# nRF52832.net
KiCad netlist of a schematic drawn in Altium Designer
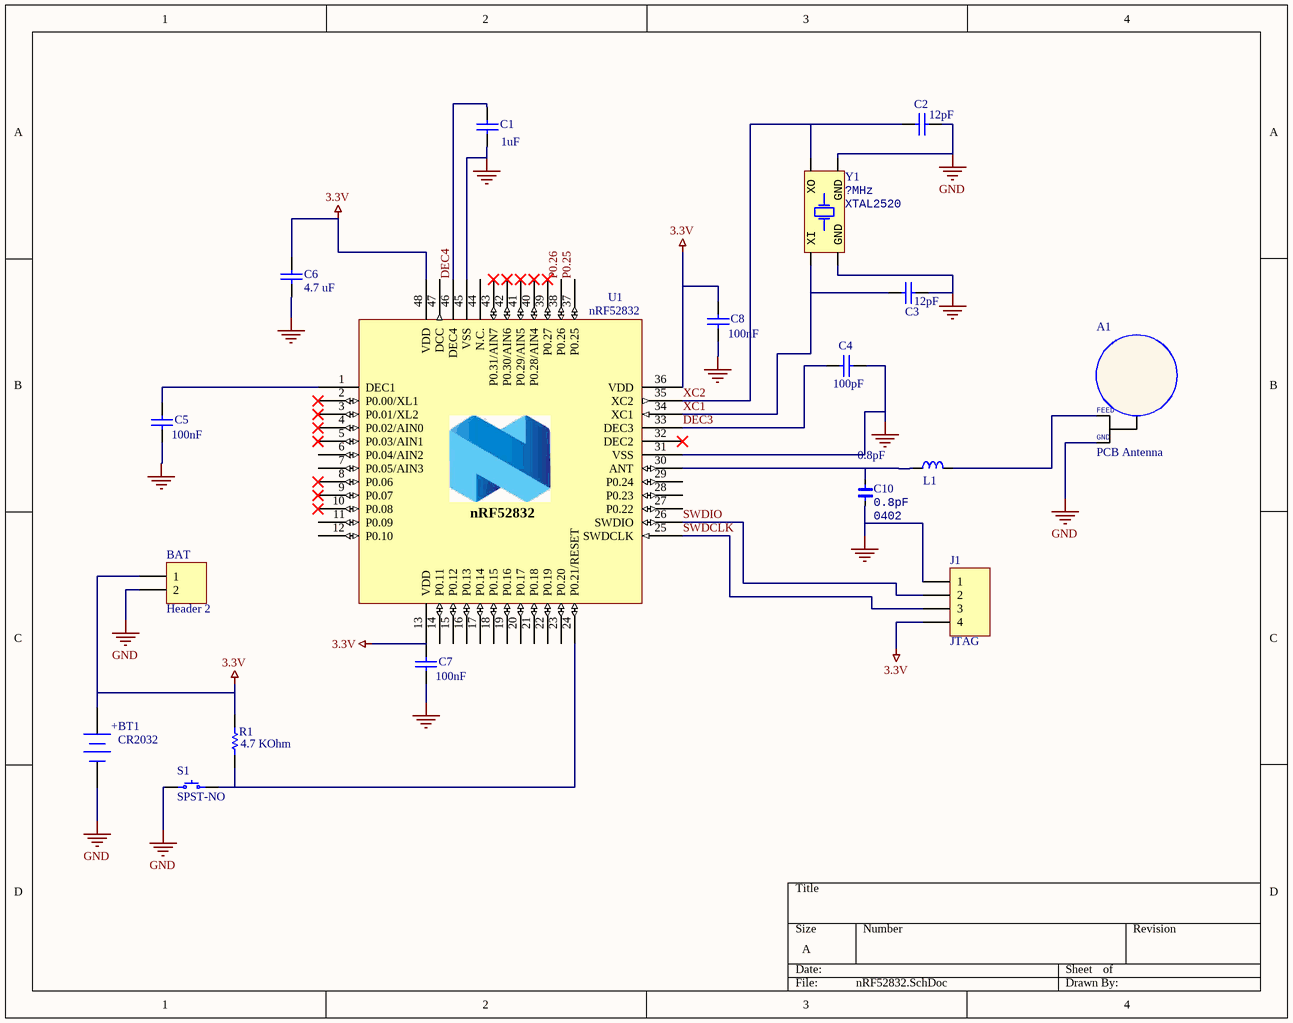
[diagram p0: nRF52832.SchDoc]

(export (version "E")
  (design (tool "Eeschema 10.0.6"))
  (components
    (comp (ref "A1")
      (value "PCB Antenna")
      (footprint "BLE_MIFA")
      (libsource (lib "Antenna") (part "BLE_MIFA"))
    )
    (comp (ref "BAT")
      (value "Header 2")
      (footprint "HDR1X2")
      (description "Header, 2-Pin")
      (libsource (lib "Miscellaneous Connectors") (part "Header 2"))
    )
    (comp (ref "BT1")
      (value "CR2032")
      (footprint "CR2032-1")
      (description "CR2032 Cell Holder")
      (fields (field (name "PUBLISHER") "Cynetik Group"))
      (libsource (lib "Battery Holder") (part "CR2032 Cell Holder"))
    )
    (comp (ref "C1")
      (value "1uF")
      (footprint "CAPC1608X90X35LL10T15")
      (fields
        (field (name "MANUFACTURER") "Murata")
        (field (name "PART NUMBER") "GRM188R61E105KA12D")
        (field (name "TOLERANCE") "10%")
      )
      (libsource (lib "Altium Content Vault") (part "CAP"))
    )
    (comp (ref "C2")
      (value "12pF")
      (footprint "CAPC1005X55X25ML05T10")
      (fields
        (field (name "PART NUMBER") "GRM1555C1H120GA01D")
        (field (name "MANUFACTURER") "Murata")
        (field (name "TOLERANCE") "2%")
      )
      (libsource (lib "Altium Content Vault") (part "CAP"))
    )
    (comp (ref "C3")
      (value "12pF")
      (footprint "CAPC1005X55X25ML05T10")
      (fields
        (field (name "PART NUMBER") "GRM1555C1H120GA01D")
        (field (name "MANUFACTURER") "Murata")
        (field (name "TOLERANCE") "2%")
      )
      (libsource (lib "Altium Content Vault") (part "CAP"))
    )
    (comp (ref "C4")
      (value "100pF")
      (footprint "CAPC1005X55X25ML05T10")
      (fields
        (field (name "MANUFACTURER") "Murata")
        (field (name "PART NUMBER") "GRM1555C1H101JA01D")
        (field (name "TOLERANCE") "5%")
      )
      (libsource (lib "Altium Content Vault") (part "CAP"))
    )
    (comp (ref "C5")
      (value "100nF")
      (footprint "CAPC1005X55X30LL05T10")
      (fields
        (field (name "MANUFACTURER") "Kemet")
        (field (name "PART NUMBER") "C0402C104K4RACTU")
        (field (name "MANUFACTURER PART NUMBER") "C0402C104K4RAC-TU")
      )
      (libsource (lib "Altium Content Vault") (part "CAP"))
    )
    (comp (ref "C6")
      (value "4.7 uF")
      (footprint "CAPC1608X90X35NL10T15")
      (description "Chip Capacitor, 4.7 uF, +/- 10%, 6.3 V, -55 to 85 degC, 0603 (1608 Metric), RoHS, Tape and Reel")
      (fields (field (name "PARTNUMBER") "GRM188R60J475KE19D") (field (name "TOLERANCE") "10%"))
      (libsource (lib "Altium Content Vault") (part "CAP-NP-2"))
    )
    (comp (ref "C7")
      (value "100nF")
      (footprint "CAPC1005X55X30LL05T10")
      (fields
        (field (name "MANUFACTURER") "Kemet")
        (field (name "PART NUMBER") "C0402C104K4RACTU")
        (field (name "MANUFACTURER PART NUMBER") "C0402C104K4RAC-TU")
      )
      (libsource (lib "Altium Content Vault") (part "CAP"))
    )
    (comp (ref "C8")
      (value "100nF")
      (footprint "CAPC1005X55X30LL05T10")
      (fields
        (field (name "MANUFACTURER") "Kemet")
        (field (name "PART NUMBER") "C0402C104K4RACTU")
        (field (name "MANUFACTURER PART NUMBER") "C0402C104K4RAC-TU")
      )
      (libsource (lib "Altium Content Vault") (part "CAP"))
    )
    (comp (ref "C10")
      (value "0.8pF")
      (footprint "0402_1x0.5x0.5mm")
      (description "Capacitor")
      (fields
        (field (name "TYPE") "0402")
        (field (name "MANUFACTURER PART NUMBER") "04023J0R8ABSTR")
        (field (name "CAPACITANCE") "0.8pF")
        (field (name "VOLTAGE") "25V")
      )
      (libsource (lib "Capacitors") (part "Cap_0402"))
    )
    (comp (ref "J1") (value "JTAG") (footprint "HDR1X4") (libsource (lib "Connectors") (part "JTAG")))
    (comp (ref "L1")
      (value "SMD_Inductor")
      (footprint "FER 0402/1005")
      (libsource (lib "Inductor") (part "SMD_Inductor"))
    )
    (comp (ref "R1")
      (value "4.7 KOhm")
      (footprint "RESC1005X40X25LL05T05")
      (description "Chip Resistor, 4.7 KOhm, +/- 1%, 63 mW, -55 to 155 degC, 0402 (1005 Metric), RoHS, Tape and Reel")
      (fields (field (name "PARTNUMBER") "CRCW04024K70FKED") (field (name "TOLERANCE") "1%"))
      (libsource (lib "Altium Content Vault") (part "RES"))
    )
    (comp (ref "S1")
      (value "SPST-NO")
      (footprint "C&K KXT")
      (fields (field (name "MANUFACTURER PART NUMBER") "KXT 331 LHS"))
      (libsource (lib "Button") (part "SPST-NO 2 PIN"))
    )
    (comp (ref "U1")
      (value "nRF52832")
      (footprint "nRF52832_QFAA")
      (fields
        (field (name "MANUFACTURER") "Nordic Semiconductor")
        (field (name "MANUFACTURER PART NUMBER") "NRF52832-QFAA-R7")
      )
      (libsource (lib "IC") (part "nRF52832_QFN"))
    )
    (comp (ref "Y1")
      (value "?MHz")
      (footprint "XT_2520_4")
      (description "Crystal Oscillator")
      (fields (field (name "TYPE") "XTAL2520") (field (name "Comment") "XTAL2520"))
      (libsource (lib "Quartz crystals") (part "XTAL_2520_4P"))
    )
  )
  (nets
    (net (code "1") (name "/DEC3") (class "Default")
      (node (ref "C4") (pin "1") (pinfunction "1_1") (pintype "passive"))
      (node (ref "U1") (pin "33") (pinfunction "DEC3_33") (pintype "power_in"))
    )
    (net (code "2") (name "/DEC4") (class "Default")
      (node (ref "C1") (pin "2") (pinfunction "2_2") (pintype "passive"))
      (node (ref "U1") (pin "46") (pinfunction "DEC4_46") (pintype "power_in"))
    )
    (net (code "3") (name "/P0.25") (class "Default")
      (node (ref "U1") (pin "37") (pinfunction "P0.25_37") (pintype "bidirectional"))
    )
    (net (code "4") (name "/P0.26") (class "Default")
      (node (ref "U1") (pin "38") (pinfunction "P0.26_38") (pintype "bidirectional"))
    )
    (net (code "5") (name "/SWDCLK") (class "Default")
      (node (ref "J1") (pin "3") (pinfunction "3_3") (pintype "passive"))
      (node (ref "U1") (pin "25") (pinfunction "SWDCLK_25") (pintype "input"))
    )
    (net (code "6") (name "/SWDIO") (class "Default")
      (node (ref "J1") (pin "2") (pinfunction "2_2") (pintype "passive"))
      (node (ref "U1") (pin "26") (pinfunction "SWDIO_26") (pintype "bidirectional"))
    )
    (net (code "7") (name "/XC1") (class "Default")
      (node (ref "C3") (pin "1") (pinfunction "1_1") (pintype "passive"))
      (node (ref "U1") (pin "34") (pinfunction "XC1_34") (pintype "input"))
      (node (ref "Y1") (pin "1") (pinfunction "XI_1") (pintype "passive"))
    )
    (net (code "8") (name "/XC2") (class "Default")
      (node (ref "C2") (pin "1") (pinfunction "1_1") (pintype "passive"))
      (node (ref "U1") (pin "35") (pinfunction "XC2_35") (pintype "output"))
      (node (ref "Y1") (pin "3") (pinfunction "XO_3") (pintype "passive"))
    )
    (net (code "9") (name "3.3V") (class "Default")
      (node (ref "BAT") (pin "1") (pinfunction "1_1") (pintype "passive"))
      (node (ref "BT1") (pin "1") (pinfunction "+_1") (pintype "passive"))
      (node (ref "C6") (pin "2") (pinfunction "2_2") (pintype "passive"))
      (node (ref "C7") (pin "2") (pinfunction "2_2") (pintype "passive"))
      (node (ref "C8") (pin "2") (pinfunction "2_2") (pintype "passive"))
      (node (ref "J1") (pin "4") (pinfunction "4_4") (pintype "passive"))
      (node (ref "R1") (pin "2") (pinfunction "2_2") (pintype "passive"))
      (node (ref "U1") (pin "13") (pinfunction "VDD_13") (pintype "power_in"))
      (node (ref "U1") (pin "36") (pinfunction "VDD_36") (pintype "power_in"))
      (node (ref "U1") (pin "48") (pinfunction "VDD_48") (pintype "power_in"))
    )
    (net (code "10") (name "GND") (class "Default")
      (node (ref "A1") (pin "0") (pinfunction "GND_0") (pintype "passive"))
      (node (ref "BAT") (pin "2") (pinfunction "2_2") (pintype "passive"))
      (node (ref "BT1") (pin "2") (pinfunction "-_2") (pintype "passive"))
      (node (ref "C1") (pin "1") (pinfunction "1_1") (pintype "passive"))
      (node (ref "C10") (pin "1") (pinfunction "1_1") (pintype "passive"))
      (node (ref "C2") (pin "2") (pinfunction "2_2") (pintype "passive"))
      (node (ref "C3") (pin "2") (pinfunction "2_2") (pintype "passive"))
      (node (ref "C4") (pin "2") (pinfunction "2_2") (pintype "passive"))
      (node (ref "C5") (pin "1") (pinfunction "1_1") (pintype "passive"))
      (node (ref "C6") (pin "1") (pinfunction "1_1") (pintype "passive"))
      (node (ref "C7") (pin "1") (pinfunction "1_1") (pintype "passive"))
      (node (ref "C8") (pin "1") (pinfunction "1_1") (pintype "passive"))
      (node (ref "J1") (pin "1") (pinfunction "1_1") (pintype "passive"))
      (node (ref "S1") (pin "1") (pinfunction "1_1") (pintype "passive"))
      (node (ref "U1") (pin "31") (pinfunction "VSS_31") (pintype "power_in"))
      (node (ref "U1") (pin "45") (pinfunction "VSS_45") (pintype "power_in"))
      (node (ref "Y1") (pin "2") (pinfunction "GND_2") (pintype "passive"))
      (node (ref "Y1") (pin "4") (pinfunction "GND_4") (pintype "passive"))
    )
    (net (code "11") (name "Net-(A1-Feed)") (class "Default")
      (node (ref "A1") (pin "1") (pinfunction "Feed_1") (pintype "passive"))
      (node (ref "L1") (pin "2") (pinfunction "2_2") (pintype "passive"))
    )
    (net (code "12") (name "Net-(U1-ANT)") (class "Default")
      (node (ref "C10") (pin "2") (pinfunction "2_2") (pintype "passive"))
      (node (ref "L1") (pin "1") (pinfunction "1_1") (pintype "passive"))
      (node (ref "U1") (pin "30") (pinfunction "ANT_30") (pintype "bidirectional"))
    )
    (net (code "13") (name "Net-(U1-DEC1)") (class "Default")
      (node (ref "C5") (pin "2") (pinfunction "2_2") (pintype "passive"))
      (node (ref "U1") (pin "1") (pinfunction "DEC1_1") (pintype "power_in"))
    )
    (net (code "14") (name "Net-(U1-P0.21{slash}RESET)") (class "Default")
      (node (ref "R1") (pin "1") (pinfunction "1_1") (pintype "passive"))
      (node (ref "S1") (pin "2") (pinfunction "2_2") (pintype "passive"))
      (node (ref "U1") (pin "24") (pinfunction "P0.21/RESET_24") (pintype "bidirectional"))
    )
    (net (code "15") (name "unconnected-(U1-DCC-Pad47)") (class "Default")
      (node (ref "U1") (pin "47") (pinfunction "DCC_47") (pintype "output"))
    )
    (net (code "16") (name "unconnected-(U1-DEC2-Pad32)") (class "Default")
      (node (ref "U1") (pin "32") (pinfunction "DEC2_32") (pintype "power_in+no_connect"))
    )
    (net (code "17") (name "unconnected-(U1-N.C.-Pad44)") (class "Default")
      (node (ref "U1") (pin "44") (pinfunction "N.C._44") (pintype "power_in"))
    )
    (net (code "18") (name "unconnected-(U1-P0.00{slash}XL1-Pad2)") (class "Default")
      (node (ref "U1") (pin "2") (pinfunction "P0.00/XL1_2") (pintype "bidirectional+no_connect"))
    )
    (net (code "19") (name "unconnected-(U1-P0.01{slash}XL2-Pad3)") (class "Default")
      (node (ref "U1") (pin "3") (pinfunction "P0.01/XL2_3") (pintype "bidirectional+no_connect"))
    )
    (net (code "20") (name "unconnected-(U1-P0.02{slash}AIN0-Pad4)") (class "Default")
      (node (ref "U1") (pin "4") (pinfunction "P0.02/AIN0_4") (pintype "bidirectional+no_connect"))
    )
    (net (code "21") (name "unconnected-(U1-P0.03{slash}AIN1-Pad5)") (class "Default")
      (node (ref "U1") (pin "5") (pinfunction "P0.03/AIN1_5") (pintype "bidirectional+no_connect"))
    )
    (net (code "22") (name "unconnected-(U1-P0.04{slash}AIN2-Pad6)") (class "Default")
      (node (ref "U1") (pin "6") (pinfunction "P0.04/AIN2_6") (pintype "bidirectional"))
    )
    (net (code "23") (name "unconnected-(U1-P0.05{slash}AIN3-Pad7)") (class "Default")
      (node (ref "U1") (pin "7") (pinfunction "P0.05/AIN3_7") (pintype "bidirectional"))
    )
    (net (code "24") (name "unconnected-(U1-P0.06-Pad8)") (class "Default")
      (node (ref "U1") (pin "8") (pinfunction "P0.06_8") (pintype "bidirectional+no_connect"))
    )
    (net (code "25") (name "unconnected-(U1-P0.07-Pad9)") (class "Default")
      (node (ref "U1") (pin "9") (pinfunction "P0.07_9") (pintype "bidirectional+no_connect"))
    )
    (net (code "26") (name "unconnected-(U1-P0.08-Pad10)") (class "Default")
      (node (ref "U1") (pin "10") (pinfunction "P0.08_10") (pintype "bidirectional+no_connect"))
    )
    (net (code "27") (name "unconnected-(U1-P0.09-Pad11)") (class "Default")
      (node (ref "U1") (pin "11") (pinfunction "P0.09_11") (pintype "bidirectional"))
    )
    (net (code "28") (name "unconnected-(U1-P0.10-Pad12)") (class "Default")
      (node (ref "U1") (pin "12") (pinfunction "P0.10_12") (pintype "bidirectional"))
    )
    (net (code "29") (name "unconnected-(U1-P0.11-Pad14)") (class "Default")
      (node (ref "U1") (pin "14") (pinfunction "P0.11_14") (pintype "bidirectional"))
    )
    (net (code "30") (name "unconnected-(U1-P0.12-Pad15)") (class "Default")
      (node (ref "U1") (pin "15") (pinfunction "P0.12_15") (pintype "bidirectional"))
    )
    (net (code "31") (name "unconnected-(U1-P0.13-Pad16)") (class "Default")
      (node (ref "U1") (pin "16") (pinfunction "P0.13_16") (pintype "bidirectional"))
    )
    (net (code "32") (name "unconnected-(U1-P0.14-Pad17)") (class "Default")
      (node (ref "U1") (pin "17") (pinfunction "P0.14_17") (pintype "bidirectional"))
    )
    (net (code "33") (name "unconnected-(U1-P0.15-Pad18)") (class "Default")
      (node (ref "U1") (pin "18") (pinfunction "P0.15_18") (pintype "bidirectional"))
    )
    (net (code "34") (name "unconnected-(U1-P0.16-Pad19)") (class "Default")
      (node (ref "U1") (pin "19") (pinfunction "P0.16_19") (pintype "bidirectional"))
    )
    (net (code "35") (name "unconnected-(U1-P0.17-Pad20)") (class "Default")
      (node (ref "U1") (pin "20") (pinfunction "P0.17_20") (pintype "bidirectional"))
    )
    (net (code "36") (name "unconnected-(U1-P0.18-Pad21)") (class "Default")
      (node (ref "U1") (pin "21") (pinfunction "P0.18_21") (pintype "bidirectional"))
    )
    (net (code "37") (name "unconnected-(U1-P0.19-Pad22)") (class "Default")
      (node (ref "U1") (pin "22") (pinfunction "P0.19_22") (pintype "bidirectional"))
    )
    (net (code "38") (name "unconnected-(U1-P0.20-Pad23)") (class "Default")
      (node (ref "U1") (pin "23") (pinfunction "P0.20_23") (pintype "bidirectional"))
    )
    (net (code "39") (name "unconnected-(U1-P0.22-Pad27)") (class "Default")
      (node (ref "U1") (pin "27") (pinfunction "P0.22_27") (pintype "bidirectional"))
    )
    (net (code "40") (name "unconnected-(U1-P0.23-Pad28)") (class "Default")
      (node (ref "U1") (pin "28") (pinfunction "P0.23_28") (pintype "bidirectional"))
    )
    (net (code "41") (name "unconnected-(U1-P0.24-Pad29)") (class "Default")
      (node (ref "U1") (pin "29") (pinfunction "P0.24_29") (pintype "bidirectional"))
    )
    (net (code "42") (name "unconnected-(U1-P0.27-Pad39)") (class "Default")
      (node (ref "U1") (pin "39") (pinfunction "P0.27_39") (pintype "bidirectional+no_connect"))
    )
    (net (code "43") (name "unconnected-(U1-P0.28{slash}AIN4-Pad40)") (class "Default")
      (node (ref "U1") (pin "40") (pinfunction "P0.28/AIN4_40") (pintype "bidirectional+no_connect"))
    )
    (net (code "44") (name "unconnected-(U1-P0.29{slash}AIN5-Pad41)") (class "Default")
      (node (ref "U1") (pin "41") (pinfunction "P0.29/AIN5_41") (pintype "bidirectional+no_connect"))
    )
    (net (code "45") (name "unconnected-(U1-P0.30{slash}AIN6-Pad42)") (class "Default")
      (node (ref "U1") (pin "42") (pinfunction "P0.30/AIN6_42") (pintype "bidirectional+no_connect"))
    )
    (net (code "46") (name "unconnected-(U1-P0.31{slash}AIN7-Pad43)") (class "Default")
      (node (ref "U1") (pin "43") (pinfunction "P0.31/AIN7_43") (pintype "bidirectional+no_connect"))
    )
  )
)
